# StartButton.net
KiCad netlist of a schematic drawn in Altium Designer
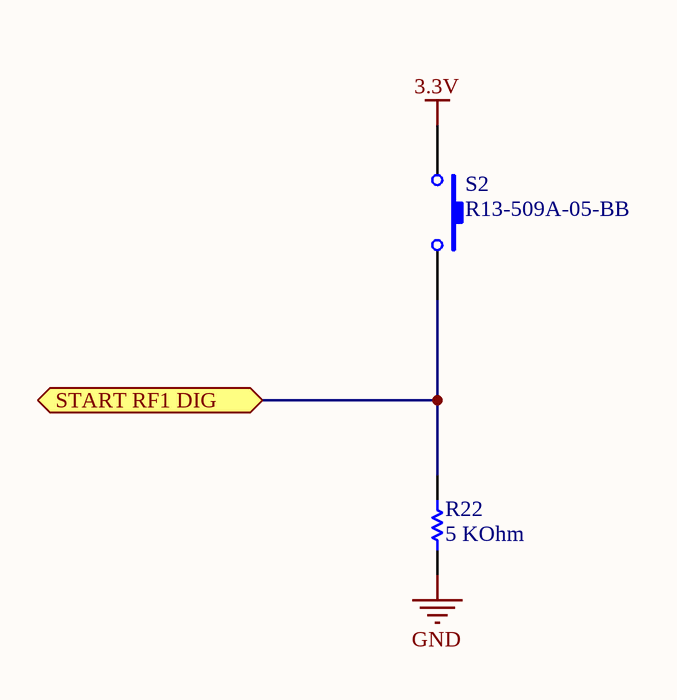
[diagram p0: StartButton.SchDoc]

(export (version "E")
  (design (tool "Eeschema 10.0.6"))
  (components
    (comp (ref "R22")
      (value "5 KOhm")
      (footprint "Resistor0603")
      (description "Resistor")
      (fields (field (name "PUBLISHER") "Altium Limited"))
      (libsource (lib "Miscellaneous Devices") (part "Res1"))
    )
    (comp (ref "S2")
      (value "R13-509A-05-BB")
      (footprint "StartButton")
      (description "Switch")
      (fields (field (name "PUBLISHER") "Altium Limited"))
      (libsource (lib "Miscellaneous Devices") (part "SW-PB"))
    )
  )
  (nets
    (net (code "1") (name "/START RF1 DIG") (class "Default")
      (node (ref "R22") (pin "2") (pinfunction "2_2") (pintype "passive"))
      (node (ref "S2") (pin "2") (pinfunction "2_2") (pintype "passive"))
    )
    (net (code "2") (name "3.3V") (class "Default")
      (node (ref "S2") (pin "1") (pinfunction "1_1") (pintype "passive"))
    )
    (net (code "3") (name "GND") (class "Default")
      (node (ref "R22") (pin "1") (pinfunction "1_1") (pintype "passive"))
    )
  )
)
